# Sigfox_Featherwing.net
KiCad netlist of a schematic drawn in EAGLE
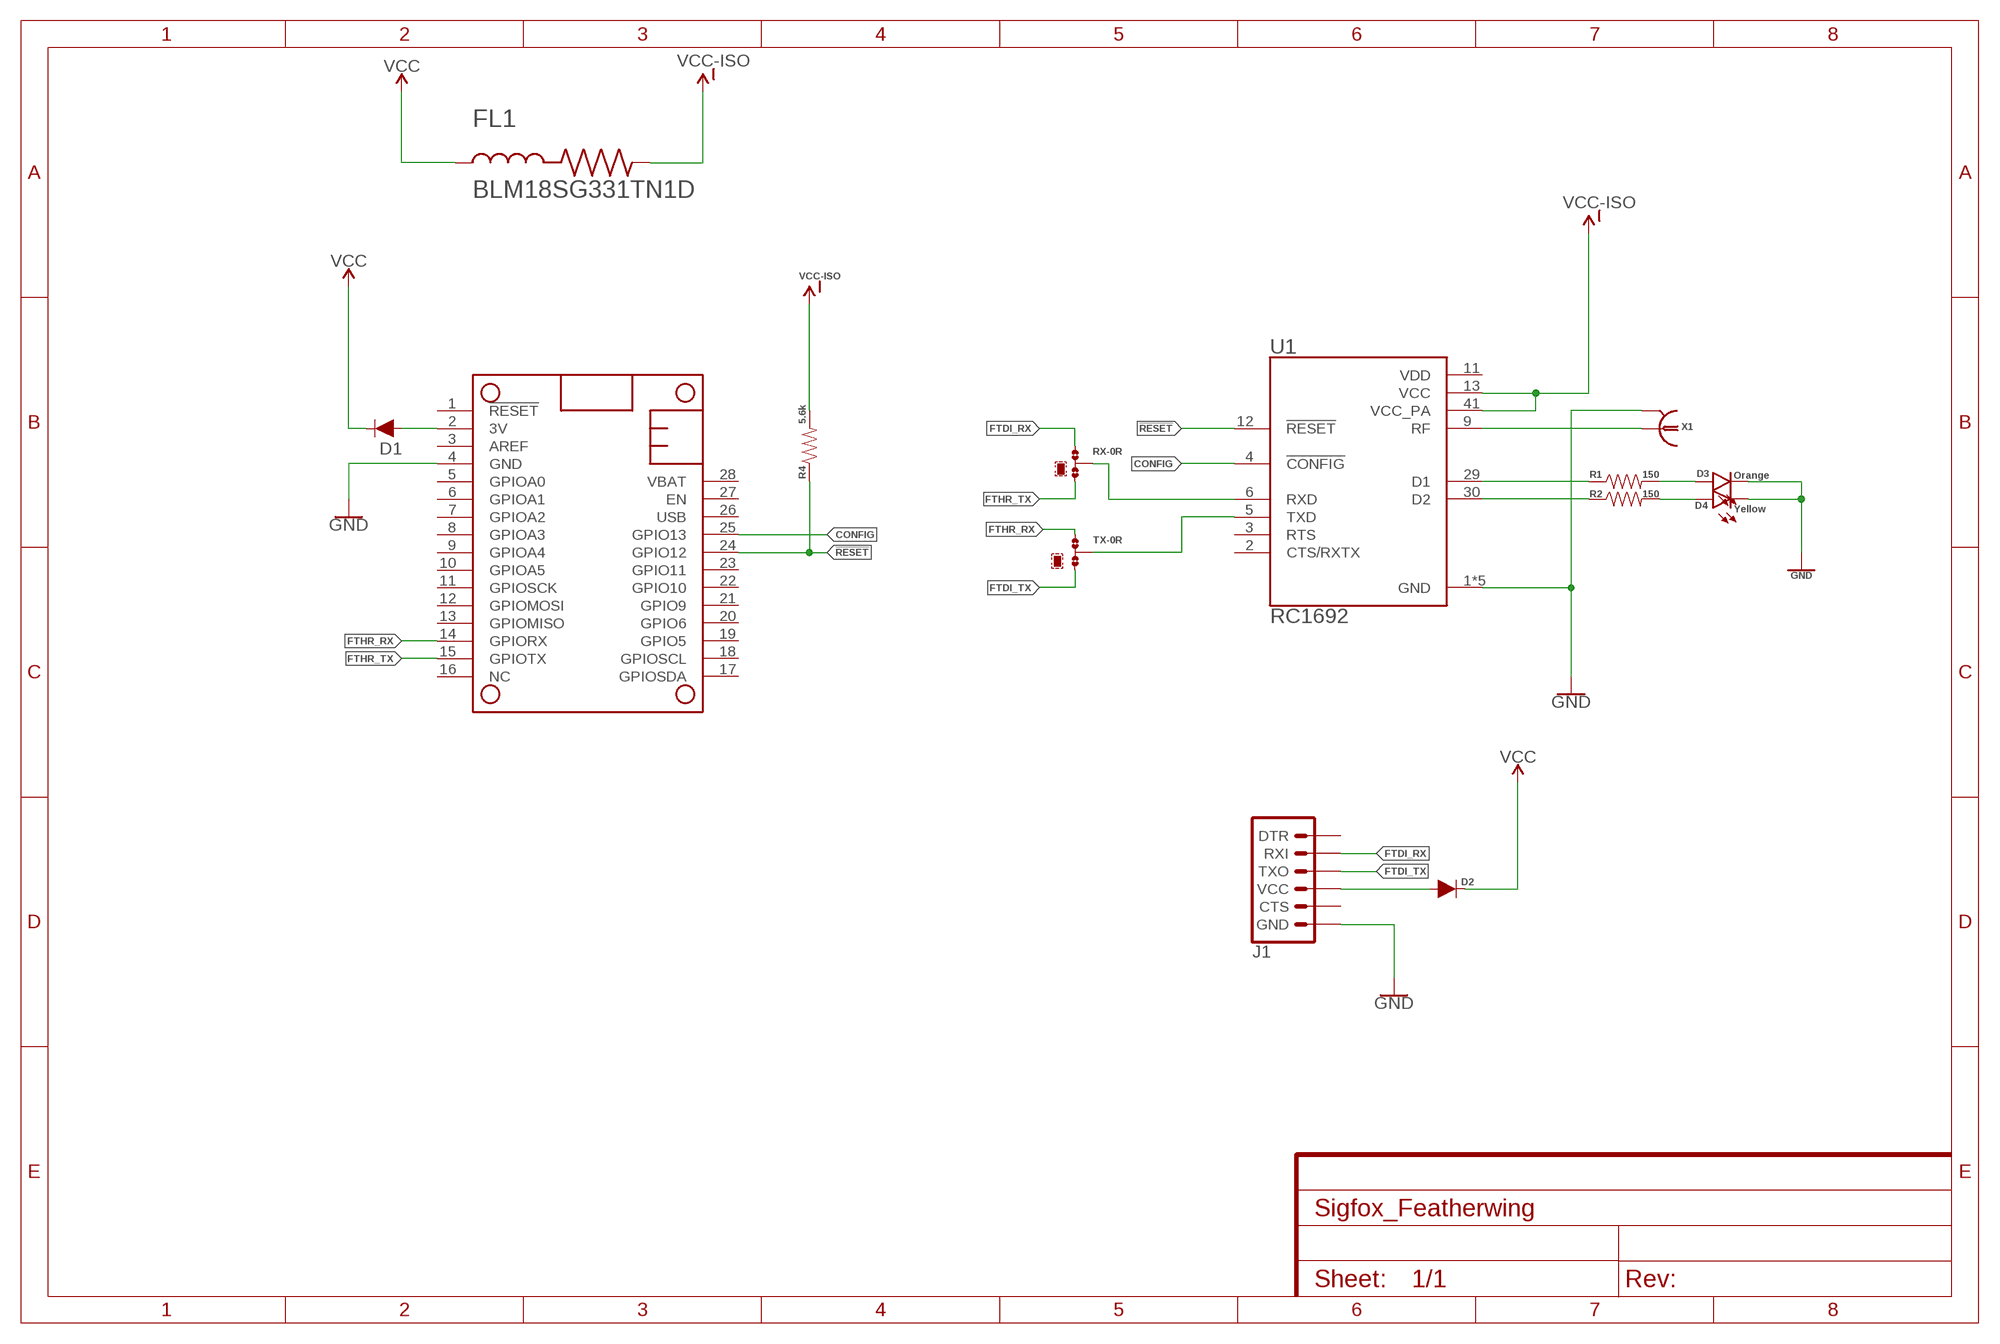
[diagram p0: schematic, sheet 1]

(export (version "E")
  (design (tool "Eeschema 10.0.6"))
  (components
    (comp (ref "D1")
      (value "250mA/100V")
      (footprint "eagle-import:SOD-323")
      (libsource (lib "eagle-import") (part "DIODE-BAS16J"))
    )
    (comp (ref "D2")
      (value "250mA/100V")
      (footprint "eagle-import:SOD-323")
      (libsource (lib "eagle-import") (part "DIODE-BAS16J"))
    )
    (comp (ref "D3")
      (value "Orange")
      (footprint "eagle-import:LED-0603")
      (libsource (lib "eagle-import") (part "LED-YELLOW0603"))
    )
    (comp (ref "D4")
      (value "Yellow")
      (footprint "eagle-import:LED-0603")
      (libsource (lib "eagle-import") (part "LED-YELLOW0603"))
    )
    (comp (ref "FL1")
      (value "BLM18SG331TN1D")
      (footprint "eagle-import:BEADC1608X65N")
      (fields (field (name "MF") "Murata Electronics"))
      (libsource (lib "eagle-import") (part "BLM18SG331TN1D"))
    )
    (comp (ref "J1")
      (value "6_PIN_SERIAL_TARGETSILK")
      (footprint "eagle-import:6_PIN_SERIAL_TARGET_SIDE_W_SILK")
      (libsource (lib "eagle-import") (part "6_PIN_SERIAL_TARGETSILK"))
    )
    (comp (ref "MS1")
      (value "FEATHERWING")
      (footprint "eagle-import:FEATHERWING")
      (libsource (lib "eagle-import") (part "FEATHERWING"))
    )
    (comp (ref "R1")
      (value "150")
      (footprint "eagle-import:0603")
      (libsource (lib "eagle-import") (part "150OHM-0603-1/10W-1%"))
    )
    (comp (ref "R2")
      (value "150")
      (footprint "eagle-import:0603")
      (libsource (lib "eagle-import") (part "150OHM-0603-1/10W-1%"))
    )
    (comp (ref "R4")
      (value "5.6k")
      (footprint "eagle-import:0603")
      (libsource (lib "eagle-import") (part "5.6KOHM-0603-1/10W-1%"))
    )
    (comp (ref "RX")
      (value "0R-JUMPB")
      (footprint "eagle-import:B0R-JMP")
      (libsource (lib "eagle-import") (part "0R-JUMPB"))
    )
    (comp (ref "TX")
      (value "0R-JUMPB")
      (footprint "eagle-import:B0R-JMP")
      (libsource (lib "eagle-import") (part "0R-JUMPB"))
    )
    (comp (ref "U1")
      (value "RC1692")
      (footprint "eagle-import:MODULE_RC1682-SIG")
      (fields (field (name "MF") "Radiocrafts AS") (field (name "MP") "RC1682-SIG"))
      (libsource (lib "eagle-import") (part "RC1692"))
    )
    (comp (ref "X1")
      (value "SMA-SMD")
      (footprint "eagle-import:SMA-SMD")
      (libsource (lib "eagle-import") (part "SMA-SMD"))
    )
  )
  (nets
    (net (code "1") (name "/USB") (class "Default")
      (node (ref "MS1") (pin "26") (pinfunction "USB_26") (pintype "power_in"))
    )
    (net (code "2") (name "/VBAT") (class "Default")
      (node (ref "MS1") (pin "28") (pinfunction "VBAT_28") (pintype "power_in"))
    )
    (net (code "3") (name "/VDD") (class "Default")
      (node (ref "U1") (pin "11") (pinfunction "VDD_11") (pintype "power_in"))
    )
    (net (code "4") (name "/~{RESET}") (class "Default")
      (node (ref "MS1") (pin "24") (pinfunction "GPIO12_24") (pintype "bidirectional"))
      (node (ref "R4") (pin "1") (pinfunction "1_1") (pintype "passive"))
      (node (ref "U1") (pin "12") (pinfunction "~{RESET}_12") (pintype "input"))
    )
    (net (code "5") (name "CONFIG") (class "Default")
      (node (ref "MS1") (pin "25") (pinfunction "GPIO13_25") (pintype "bidirectional"))
      (node (ref "U1") (pin "4") (pinfunction "~{CONFIG}_4") (pintype "input"))
    )
    (net (code "6") (name "FTDI_RX") (class "Default")
      (node (ref "J1") (pin "P$3") (pinfunction "RXI_P$3") (pintype "passive"))
      (node (ref "RX") (pin "1") (pinfunction "1_1") (pintype "passive"))
    )
    (net (code "7") (name "FTDI_TX") (class "Default")
      (node (ref "J1") (pin "P$2") (pinfunction "TXO_P$2") (pintype "passive"))
      (node (ref "TX") (pin "3") (pinfunction "3_3") (pintype "passive"))
    )
    (net (code "8") (name "FTHR_RX") (class "Default")
      (node (ref "MS1") (pin "14") (pinfunction "GPIORX_14") (pintype "bidirectional"))
      (node (ref "TX") (pin "1") (pinfunction "1_1") (pintype "passive"))
    )
    (net (code "9") (name "FTHR_TX") (class "Default")
      (node (ref "MS1") (pin "15") (pinfunction "GPIOTX_15") (pintype "bidirectional"))
      (node (ref "RX") (pin "3") (pinfunction "3_3") (pintype "passive"))
    )
    (net (code "10") (name "GND") (class "Default")
      (node (ref "D3") (pin "C") (pinfunction "C_C") (pintype "passive"))
      (node (ref "D4") (pin "C") (pinfunction "C_C") (pintype "passive"))
      (node (ref "J1") (pin "P$6") (pinfunction "GND_P$6") (pintype "passive"))
      (node (ref "MS1") (pin "4") (pinfunction "GND_4") (pintype "power_in"))
      (node (ref "U1") (pin "1") (pinfunction "GND_1") (pintype "power_in"))
      (node (ref "U1") (pin "10") (pinfunction "GND_10") (pintype "power_in"))
      (node (ref "U1") (pin "14") (pinfunction "GND_14") (pintype "power_in"))
      (node (ref "U1") (pin "7") (pinfunction "GND_7") (pintype "power_in"))
      (node (ref "U1") (pin "8") (pinfunction "GND_8") (pintype "power_in"))
      (node (ref "X1") (pin "2@1") (pinfunction "2_2@1") (pintype "passive"))
      (node (ref "X1") (pin "2@2") (pinfunction "2_2@2") (pintype "passive"))
      (node (ref "X1") (pin "2@3") (pinfunction "2_2@3") (pintype "passive"))
      (node (ref "X1") (pin "2@4") (pinfunction "2_2@4") (pintype "passive"))
      (node (ref "X1") (pin "2@5") (pinfunction "2_2@5") (pintype "passive"))
      (node (ref "X1") (pin "2@6") (pinfunction "2_2@6") (pintype "passive"))
    )
    (net (code "11") (name "Net-(D3-PadA)") (class "Default")
      (node (ref "D3") (pin "A") (pinfunction "A_A") (pintype "passive"))
      (node (ref "R1") (pin "2") (pinfunction "2_2") (pintype "passive"))
    )
    (net (code "12") (name "Net-(D4-PadA)") (class "Default")
      (node (ref "D4") (pin "A") (pinfunction "A_A") (pintype "passive"))
      (node (ref "R2") (pin "2") (pinfunction "2_2") (pintype "passive"))
    )
    (net (code "13") (name "Net-(J1-VCC)") (class "Default")
      (node (ref "D2") (pin "A") (pinfunction "A_A") (pintype "passive"))
      (node (ref "J1") (pin "P$4") (pinfunction "VCC_P$4") (pintype "passive"))
    )
    (net (code "14") (name "Net-(MS1-3V)") (class "Default")
      (node (ref "D1") (pin "A") (pinfunction "A_A") (pintype "passive"))
      (node (ref "MS1") (pin "2") (pinfunction "3V_2") (pintype "power_in"))
    )
    (net (code "15") (name "Net-(U1-D1)") (class "Default")
      (node (ref "R1") (pin "1") (pinfunction "1_1") (pintype "passive"))
      (node (ref "U1") (pin "29") (pinfunction "D1_29") (pintype "bidirectional"))
    )
    (net (code "16") (name "Net-(U1-D2)") (class "Default")
      (node (ref "R2") (pin "1") (pinfunction "1_1") (pintype "passive"))
      (node (ref "U1") (pin "30") (pinfunction "D2_30") (pintype "bidirectional"))
    )
    (net (code "17") (name "Net-(U1-RF)") (class "Default")
      (node (ref "U1") (pin "9") (pinfunction "RF_9") (pintype "bidirectional"))
      (node (ref "X1") (pin "1") (pinfunction "1_1") (pintype "passive"))
    )
    (net (code "18") (name "Net-(U1-RXD)") (class "Default")
      (node (ref "RX") (pin "2") (pinfunction "2_2") (pintype "passive"))
      (node (ref "U1") (pin "6") (pinfunction "RXD_6") (pintype "input"))
    )
    (net (code "19") (name "Net-(U1-TXD)") (class "Default")
      (node (ref "TX") (pin "2") (pinfunction "2_2") (pintype "passive"))
      (node (ref "U1") (pin "5") (pinfunction "TXD_5") (pintype "output"))
    )
    (net (code "20") (name "VCC") (class "Default")
      (node (ref "D1") (pin "C") (pinfunction "C_C") (pintype "passive"))
      (node (ref "D2") (pin "C") (pinfunction "C_C") (pintype "passive"))
      (node (ref "FL1") (pin "1") (pinfunction "1_1") (pintype "passive"))
    )
    (net (code "21") (name "VCC-ISO") (class "Default")
      (node (ref "FL1") (pin "2") (pinfunction "2_2") (pintype "passive"))
      (node (ref "R4") (pin "2") (pinfunction "2_2") (pintype "passive"))
      (node (ref "U1") (pin "13") (pinfunction "VCC_13") (pintype "power_in"))
      (node (ref "U1") (pin "41") (pinfunction "VCC_PA_41") (pintype "power_in"))
    )
    (net (code "22") (name "unconnected-(J1-CTS-PadP$5)") (class "Default")
      (node (ref "J1") (pin "P$5") (pinfunction "CTS_P$5") (pintype "passive"))
    )
    (net (code "23") (name "unconnected-(J1-DTR-PadP$1)") (class "Default")
      (node (ref "J1") (pin "P$1") (pinfunction "DTR_P$1") (pintype "passive"))
    )
    (net (code "24") (name "unconnected-(MS1-AREF-Pad3)") (class "Default")
      (node (ref "MS1") (pin "3") (pinfunction "AREF_3") (pintype "passive"))
    )
    (net (code "25") (name "unconnected-(MS1-EN-Pad27)") (class "Default")
      (node (ref "MS1") (pin "27") (pinfunction "EN_27") (pintype "passive"))
    )
    (net (code "26") (name "unconnected-(MS1-GPIO5-Pad19)") (class "Default")
      (node (ref "MS1") (pin "19") (pinfunction "GPIO5_19") (pintype "bidirectional"))
    )
    (net (code "27") (name "unconnected-(MS1-GPIO6-Pad20)") (class "Default")
      (node (ref "MS1") (pin "20") (pinfunction "GPIO6_20") (pintype "bidirectional"))
    )
    (net (code "28") (name "unconnected-(MS1-GPIO9-Pad21)") (class "Default")
      (node (ref "MS1") (pin "21") (pinfunction "GPIO9_21") (pintype "bidirectional"))
    )
    (net (code "29") (name "unconnected-(MS1-GPIO10-Pad22)") (class "Default")
      (node (ref "MS1") (pin "22") (pinfunction "GPIO10_22") (pintype "bidirectional"))
    )
    (net (code "30") (name "unconnected-(MS1-GPIO11-Pad23)") (class "Default")
      (node (ref "MS1") (pin "23") (pinfunction "GPIO11_23") (pintype "bidirectional"))
    )
    (net (code "31") (name "unconnected-(MS1-GPIOA0-Pad5)") (class "Default")
      (node (ref "MS1") (pin "5") (pinfunction "GPIOA0_5") (pintype "bidirectional"))
    )
    (net (code "32") (name "unconnected-(MS1-GPIOA1-Pad6)") (class "Default")
      (node (ref "MS1") (pin "6") (pinfunction "GPIOA1_6") (pintype "bidirectional"))
    )
    (net (code "33") (name "unconnected-(MS1-GPIOA2-Pad7)") (class "Default")
      (node (ref "MS1") (pin "7") (pinfunction "GPIOA2_7") (pintype "bidirectional"))
    )
    (net (code "34") (name "unconnected-(MS1-GPIOA3-Pad8)") (class "Default")
      (node (ref "MS1") (pin "8") (pinfunction "GPIOA3_8") (pintype "bidirectional"))
    )
    (net (code "35") (name "unconnected-(MS1-GPIOA4-Pad9)") (class "Default")
      (node (ref "MS1") (pin "9") (pinfunction "GPIOA4_9") (pintype "bidirectional"))
    )
    (net (code "36") (name "unconnected-(MS1-GPIOA5-Pad10)") (class "Default")
      (node (ref "MS1") (pin "10") (pinfunction "GPIOA5_10") (pintype "bidirectional"))
    )
    (net (code "37") (name "unconnected-(MS1-GPIOMISO-Pad13)") (class "Default")
      (node (ref "MS1") (pin "13") (pinfunction "GPIOMISO_13") (pintype "bidirectional"))
    )
    (net (code "38") (name "unconnected-(MS1-GPIOMOSI-Pad12)") (class "Default")
      (node (ref "MS1") (pin "12") (pinfunction "GPIOMOSI_12") (pintype "bidirectional"))
    )
    (net (code "39") (name "unconnected-(MS1-GPIOSCK-Pad11)") (class "Default")
      (node (ref "MS1") (pin "11") (pinfunction "GPIOSCK_11") (pintype "bidirectional"))
    )
    (net (code "40") (name "unconnected-(MS1-GPIOSCL-Pad18)") (class "Default")
      (node (ref "MS1") (pin "18") (pinfunction "GPIOSCL_18") (pintype "bidirectional"))
    )
    (net (code "41") (name "unconnected-(MS1-GPIOSDA-Pad17)") (class "Default")
      (node (ref "MS1") (pin "17") (pinfunction "GPIOSDA_17") (pintype "bidirectional"))
    )
    (net (code "42") (name "unconnected-(MS1-NC-Pad16)") (class "Default")
      (node (ref "MS1") (pin "16") (pinfunction "NC_16") (pintype "passive"))
    )
    (net (code "43") (name "unconnected-(MS1-~{RESET}-Pad1)") (class "Default")
      (node (ref "MS1") (pin "1") (pinfunction "~{RESET}_1") (pintype "input"))
    )
    (net (code "44") (name "unconnected-(U1-CTS{slash}RXTX-Pad2)") (class "Default")
      (node (ref "U1") (pin "2") (pinfunction "CTS/RXTX_2") (pintype "bidirectional"))
    )
    (net (code "45") (name "unconnected-(U1-RTS-Pad3)") (class "Default")
      (node (ref "U1") (pin "3") (pinfunction "RTS_3") (pintype "input"))
    )
  )
)
